# GB_ROM_Adapter.net
KiCad netlist of a schematic drawn in EAGLE
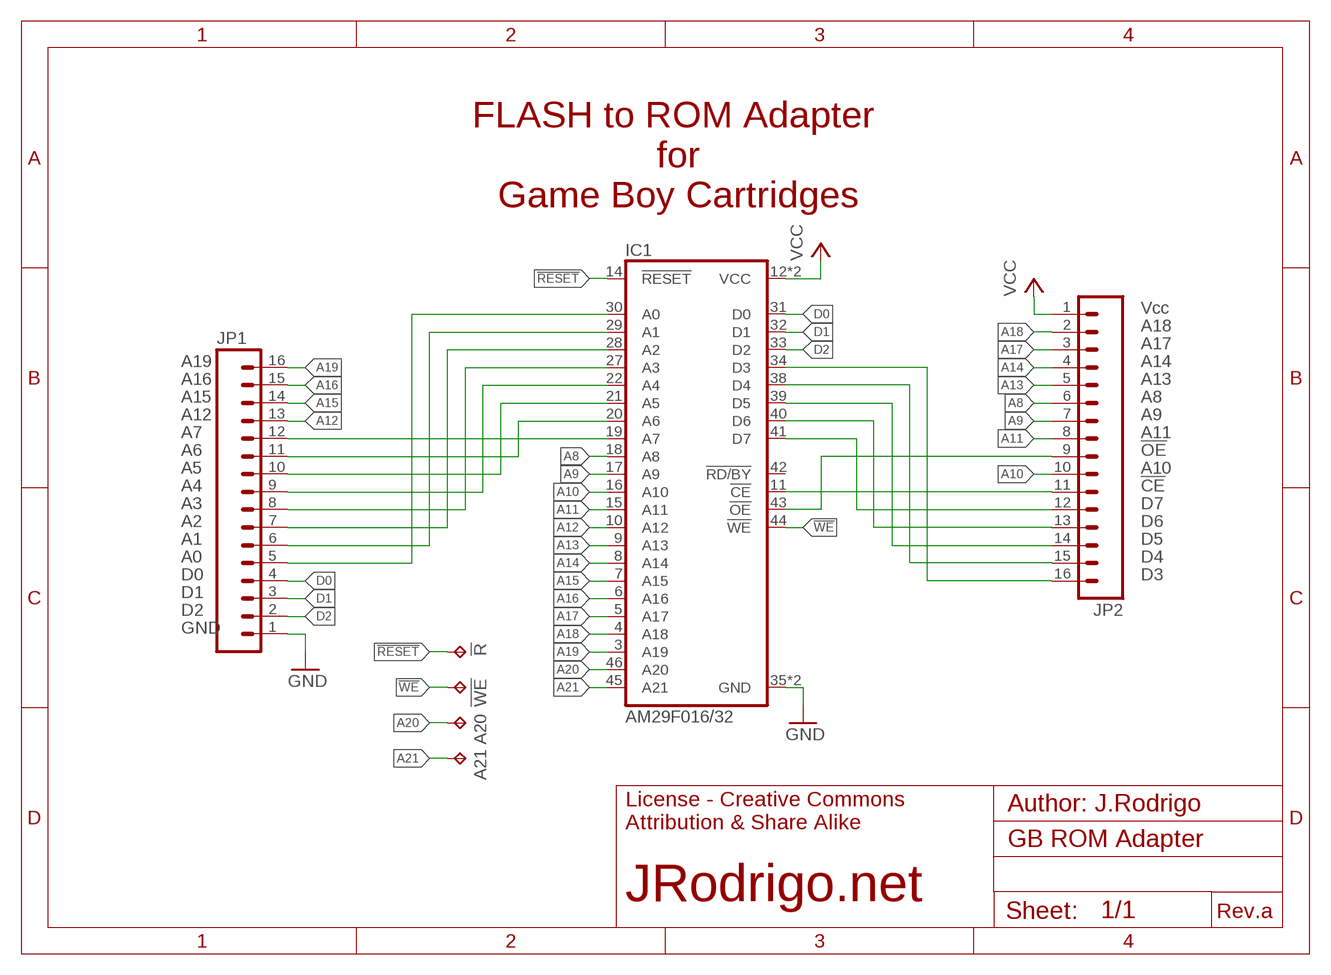
[diagram p0: schematic, sheet 1]

(export (version "E")
  (design (tool "Eeschema 10.0.6"))
  (components
    (comp (ref "!R")
      (value "TPTP08SQ")
      (footprint "eagle-import:TP08SQ")
      (libsource (lib "eagle-import") (part "TPTP08SQ"))
    )
    (comp (ref "!WE")
      (value "TPTP08SQ")
      (footprint "eagle-import:TP08SQ")
      (libsource (lib "eagle-import") (part "TPTP08SQ"))
    )
    (comp (ref "A20")
      (value "TPTP08SQ")
      (footprint "eagle-import:TP08SQ")
      (libsource (lib "eagle-import") (part "TPTP08SQ"))
    )
    (comp (ref "A21")
      (value "TPTP08SQ")
      (footprint "eagle-import:TP08SQ")
      (libsource (lib "eagle-import") (part "TPTP08SQ"))
    )
    (comp (ref "IC1")
      (value "AM29F016/32")
      (footprint "eagle-import:TSOP48")
      (libsource (lib "eagle-import") (part "AM29FXXXTSOP48-STANDARD"))
    )
    (comp (ref "JP1")
      (value "CASTELLATIONS_16-PINS*")
      (footprint "eagle-import:CASTELLATIONS_16-PINS")
      (libsource (lib "eagle-import") (part "CASTELLATIONS_16-PINS"))
    )
    (comp (ref "JP2")
      (value "CASTELLATIONS_16-PINS*")
      (footprint "eagle-import:CASTELLATIONS_16-PINS")
      (libsource (lib "eagle-import") (part "CASTELLATIONS_16-PINS"))
    )
  )
  (nets
    (net (code "1") (name "/~{RESET}") (class "Default")
      (node (ref "!R") (pin "TP") (pinfunction "TP_TP") (pintype "input"))
      (node (ref "IC1") (pin "14") (pinfunction "~{RESET}_14") (pintype "input"))
    )
    (net (code "2") (name "/~{WE}") (class "Default")
      (node (ref "!WE") (pin "TP") (pinfunction "TP_TP") (pintype "input"))
      (node (ref "IC1") (pin "44") (pinfunction "~{WE}_44") (pintype "input"))
    )
    (net (code "3") (name "A8") (class "Default")
      (node (ref "IC1") (pin "18") (pinfunction "A8_18") (pintype "input"))
      (node (ref "JP2") (pin "6") (pinfunction "6_6") (pintype "passive"))
    )
    (net (code "4") (name "A9") (class "Default")
      (node (ref "IC1") (pin "17") (pinfunction "A9_17") (pintype "input"))
      (node (ref "JP2") (pin "7") (pinfunction "7_7") (pintype "passive"))
    )
    (net (code "5") (name "A10") (class "Default")
      (node (ref "IC1") (pin "16") (pinfunction "A10_16") (pintype "input"))
      (node (ref "JP2") (pin "10") (pinfunction "10_10") (pintype "passive"))
    )
    (net (code "6") (name "A11") (class "Default")
      (node (ref "IC1") (pin "15") (pinfunction "A11_15") (pintype "input"))
      (node (ref "JP2") (pin "8") (pinfunction "8_8") (pintype "passive"))
    )
    (net (code "7") (name "A12") (class "Default")
      (node (ref "IC1") (pin "10") (pinfunction "A12_10") (pintype "input"))
      (node (ref "JP1") (pin "13") (pinfunction "13_13") (pintype "passive"))
    )
    (net (code "8") (name "A13") (class "Default")
      (node (ref "IC1") (pin "9") (pinfunction "A13_9") (pintype "input"))
      (node (ref "JP2") (pin "5") (pinfunction "5_5") (pintype "passive"))
    )
    (net (code "9") (name "A14") (class "Default")
      (node (ref "IC1") (pin "8") (pinfunction "A14_8") (pintype "input"))
      (node (ref "JP2") (pin "4") (pinfunction "4_4") (pintype "passive"))
    )
    (net (code "10") (name "A15") (class "Default")
      (node (ref "IC1") (pin "7") (pinfunction "A15_7") (pintype "input"))
      (node (ref "JP1") (pin "14") (pinfunction "14_14") (pintype "passive"))
    )
    (net (code "11") (name "A16") (class "Default")
      (node (ref "IC1") (pin "6") (pinfunction "A16_6") (pintype "input"))
      (node (ref "JP1") (pin "15") (pinfunction "15_15") (pintype "passive"))
    )
    (net (code "12") (name "A17") (class "Default")
      (node (ref "IC1") (pin "5") (pinfunction "A17_5") (pintype "input"))
      (node (ref "JP2") (pin "3") (pinfunction "3_3") (pintype "passive"))
    )
    (net (code "13") (name "A18") (class "Default")
      (node (ref "IC1") (pin "4") (pinfunction "A18_4") (pintype "input"))
      (node (ref "JP2") (pin "2") (pinfunction "2_2") (pintype "passive"))
    )
    (net (code "14") (name "A19") (class "Default")
      (node (ref "IC1") (pin "3") (pinfunction "A19_3") (pintype "input"))
      (node (ref "JP1") (pin "16") (pinfunction "16_16") (pintype "passive"))
    )
    (net (code "15") (name "A20") (class "Default")
      (node (ref "A20") (pin "TP") (pinfunction "TP_TP") (pintype "input"))
      (node (ref "IC1") (pin "46") (pinfunction "A20_46") (pintype "input"))
    )
    (net (code "16") (name "A21") (class "Default")
      (node (ref "A21") (pin "TP") (pinfunction "TP_TP") (pintype "input"))
      (node (ref "IC1") (pin "45") (pinfunction "A21_45") (pintype "input"))
    )
    (net (code "17") (name "D0") (class "Default")
      (node (ref "IC1") (pin "31") (pinfunction "D0_31") (pintype "tri_state"))
      (node (ref "JP1") (pin "4") (pinfunction "4_4") (pintype "passive"))
    )
    (net (code "18") (name "D1") (class "Default")
      (node (ref "IC1") (pin "32") (pinfunction "D1_32") (pintype "tri_state"))
      (node (ref "JP1") (pin "3") (pinfunction "3_3") (pintype "passive"))
    )
    (net (code "19") (name "D2") (class "Default")
      (node (ref "IC1") (pin "33") (pinfunction "D2_33") (pintype "tri_state"))
      (node (ref "JP1") (pin "2") (pinfunction "2_2") (pintype "passive"))
    )
    (net (code "20") (name "GND") (class "Default")
      (node (ref "IC1") (pin "35") (pinfunction "GND_35") (pintype "power_in"))
      (node (ref "IC1") (pin "36") (pinfunction "GND_36") (pintype "power_in"))
      (node (ref "JP1") (pin "1") (pinfunction "1_1") (pintype "passive"))
    )
    (net (code "21") (name "Net-(IC1-A0)") (class "Default")
      (node (ref "IC1") (pin "30") (pinfunction "A0_30") (pintype "input"))
      (node (ref "JP1") (pin "5") (pinfunction "5_5") (pintype "passive"))
    )
    (net (code "22") (name "Net-(IC1-A1)") (class "Default")
      (node (ref "IC1") (pin "29") (pinfunction "A1_29") (pintype "input"))
      (node (ref "JP1") (pin "6") (pinfunction "6_6") (pintype "passive"))
    )
    (net (code "23") (name "Net-(IC1-A2)") (class "Default")
      (node (ref "IC1") (pin "28") (pinfunction "A2_28") (pintype "input"))
      (node (ref "JP1") (pin "7") (pinfunction "7_7") (pintype "passive"))
    )
    (net (code "24") (name "Net-(IC1-A3)") (class "Default")
      (node (ref "IC1") (pin "27") (pinfunction "A3_27") (pintype "input"))
      (node (ref "JP1") (pin "8") (pinfunction "8_8") (pintype "passive"))
    )
    (net (code "25") (name "Net-(IC1-A4)") (class "Default")
      (node (ref "IC1") (pin "22") (pinfunction "A4_22") (pintype "input"))
      (node (ref "JP1") (pin "9") (pinfunction "9_9") (pintype "passive"))
    )
    (net (code "26") (name "Net-(IC1-A5)") (class "Default")
      (node (ref "IC1") (pin "21") (pinfunction "A5_21") (pintype "input"))
      (node (ref "JP1") (pin "10") (pinfunction "10_10") (pintype "passive"))
    )
    (net (code "27") (name "Net-(IC1-A6)") (class "Default")
      (node (ref "IC1") (pin "20") (pinfunction "A6_20") (pintype "input"))
      (node (ref "JP1") (pin "11") (pinfunction "11_11") (pintype "passive"))
    )
    (net (code "28") (name "Net-(IC1-A7)") (class "Default")
      (node (ref "IC1") (pin "19") (pinfunction "A7_19") (pintype "input"))
      (node (ref "JP1") (pin "12") (pinfunction "12_12") (pintype "passive"))
    )
    (net (code "29") (name "Net-(IC1-D3)") (class "Default")
      (node (ref "IC1") (pin "34") (pinfunction "D3_34") (pintype "tri_state"))
      (node (ref "JP2") (pin "16") (pinfunction "16_16") (pintype "passive"))
    )
    (net (code "30") (name "Net-(IC1-D4)") (class "Default")
      (node (ref "IC1") (pin "38") (pinfunction "D4_38") (pintype "tri_state"))
      (node (ref "JP2") (pin "15") (pinfunction "15_15") (pintype "passive"))
    )
    (net (code "31") (name "Net-(IC1-D5)") (class "Default")
      (node (ref "IC1") (pin "39") (pinfunction "D5_39") (pintype "tri_state"))
      (node (ref "JP2") (pin "14") (pinfunction "14_14") (pintype "passive"))
    )
    (net (code "32") (name "Net-(IC1-D6)") (class "Default")
      (node (ref "IC1") (pin "40") (pinfunction "D6_40") (pintype "tri_state"))
      (node (ref "JP2") (pin "13") (pinfunction "13_13") (pintype "passive"))
    )
    (net (code "33") (name "Net-(IC1-D7)") (class "Default")
      (node (ref "IC1") (pin "41") (pinfunction "D7_41") (pintype "tri_state"))
      (node (ref "JP2") (pin "12") (pinfunction "12_12") (pintype "passive"))
    )
    (net (code "34") (name "Net-(IC1-~{CE})") (class "Default")
      (node (ref "IC1") (pin "11") (pinfunction "~{CE}_11") (pintype "input"))
      (node (ref "JP2") (pin "11") (pinfunction "11_11") (pintype "passive"))
    )
    (net (code "35") (name "Net-(IC1-~{OE})") (class "Default")
      (node (ref "IC1") (pin "43") (pinfunction "~{OE}_43") (pintype "input"))
      (node (ref "JP2") (pin "9") (pinfunction "9_9") (pintype "passive"))
    )
    (net (code "36") (name "VCC") (class "Default")
      (node (ref "IC1") (pin "12") (pinfunction "VCC_12") (pintype "power_in"))
      (node (ref "IC1") (pin "37") (pinfunction "VCC_37") (pintype "power_in"))
      (node (ref "JP2") (pin "1") (pinfunction "1_1") (pintype "passive"))
    )
    (net (code "37") (name "unconnected-(IC1-~{RD{slash}BY}-Pad42)") (class "Default")
      (node (ref "IC1") (pin "42") (pinfunction "~{RD/BY}_42") (pintype "output"))
    )
  )
)
